# SSB_Transceiver_Antenna_Amplifier.net
KiCad netlist of a schematic drawn in EAGLE
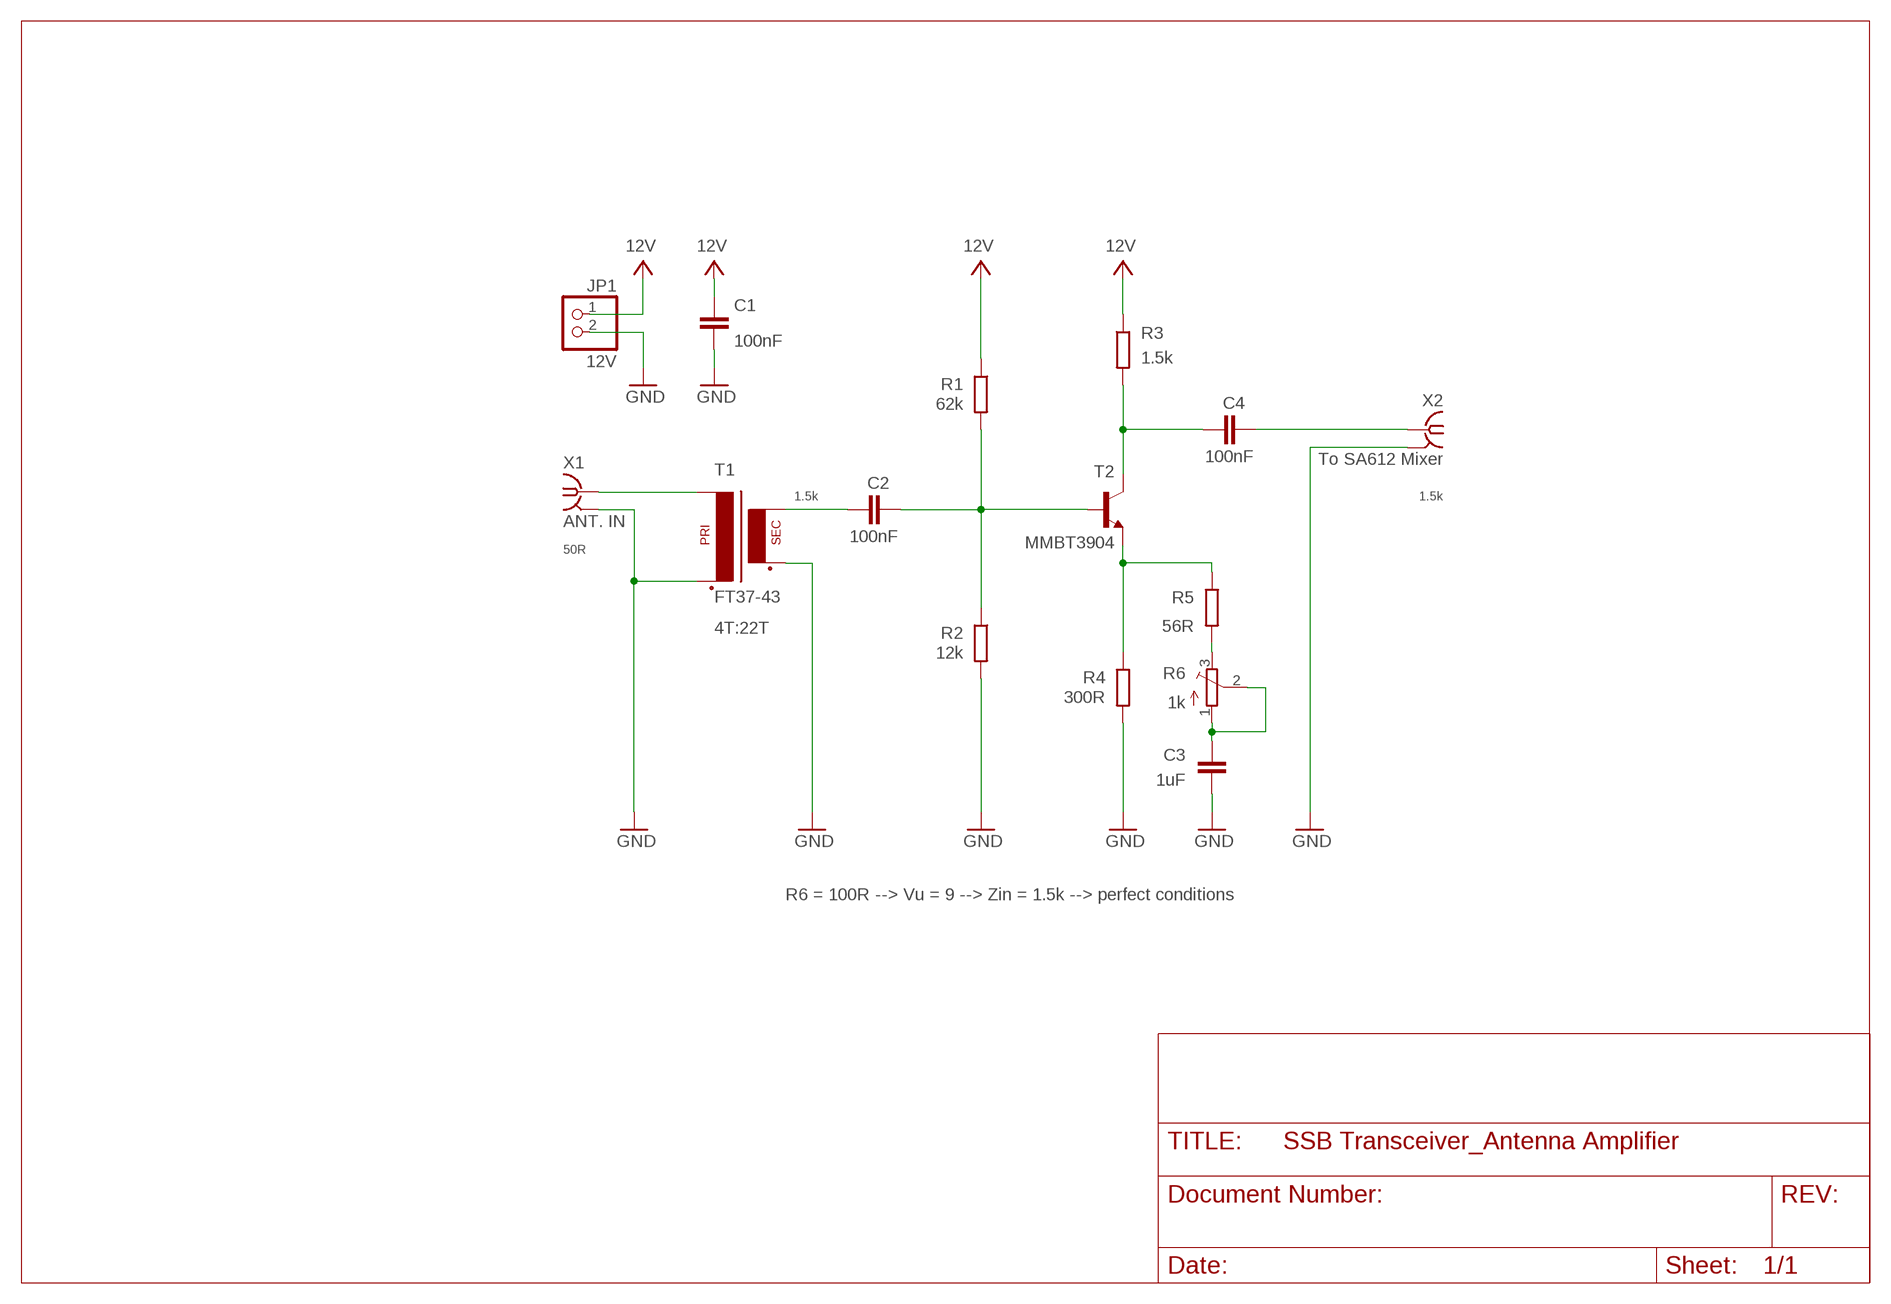
[diagram p0: schematic, sheet 1]

(export (version "E")
  (design (tool "Eeschema 10.0.6"))
  (components
    (comp (ref "C1")
      (value "100nF")
      (footprint "eagle-import:C0805")
      (libsource (lib "eagle-import") (part "C-EUC0805"))
    )
    (comp (ref "C2")
      (value "100nF")
      (footprint "eagle-import:C0805")
      (libsource (lib "eagle-import") (part "C-EUC0805"))
    )
    (comp (ref "C3")
      (value "1uF")
      (footprint "eagle-import:C0805")
      (libsource (lib "eagle-import") (part "C-EUC0805"))
    )
    (comp (ref "C4")
      (value "100nF")
      (footprint "eagle-import:C0805")
      (libsource (lib "eagle-import") (part "C-EUC0805"))
    )
    (comp (ref "JP1")
      (value "12V")
      (footprint "eagle-import:1X02")
      (libsource (lib "eagle-import") (part "PINHD-1X2"))
    )
    (comp (ref "R1")
      (value "62k")
      (footprint "eagle-import:R0805")
      (libsource (lib "eagle-import") (part "R-EU_R0805"))
    )
    (comp (ref "R2")
      (value "12k")
      (footprint "eagle-import:R0805")
      (libsource (lib "eagle-import") (part "R-EU_R0805"))
    )
    (comp (ref "R3")
      (value "1.5k")
      (footprint "eagle-import:R0805")
      (libsource (lib "eagle-import") (part "R-EU_R0805"))
    )
    (comp (ref "R4")
      (value "300R")
      (footprint "eagle-import:R0805")
      (libsource (lib "eagle-import") (part "R-EU_R0805"))
    )
    (comp (ref "R5")
      (value "56R")
      (footprint "eagle-import:R0805")
      (libsource (lib "eagle-import") (part "R-EU_R0805"))
    )
    (comp (ref "R6")
      (value "1k")
      (footprint "eagle-import:3223G")
      (libsource (lib "eagle-import") (part "TRIM_EU-3223G"))
    )
    (comp (ref "T1")
      (value "FT37-43")
      (footprint "eagle-import:FT37-43SMD")
      (libsource (lib "eagle-import") (part "FT37-43"))
    )
    (comp (ref "T2")
      (value "MMBT3904")
      (footprint "eagle-import:SOT23-BEC")
      (libsource (lib "eagle-import") (part "-NPN-SOT23-BECMMBT3904LT1"))
    )
    (comp (ref "X1")
      (value "ANT. IN")
      (footprint "eagle-import:J502-ND-142-0711-821_826")
      (fields (field (name "MF") "JOHNSON COMPONENTS") (field (name "MPN") "142-0711-821"))
      (libsource (lib "eagle-import") (part "SMA-PCB-CON142-0711-821/826"))
    )
    (comp (ref "X2")
      (value "To SA612 Mixer")
      (footprint "eagle-import:J502-ND-142-0711-821_826")
      (fields (field (name "MF") "JOHNSON COMPONENTS") (field (name "MPN") "142-0711-821"))
      (libsource (lib "eagle-import") (part "SMA-PCB-CON142-0711-821/826"))
    )
  )
  (nets
    (net (code "1") (name "12V") (class "Default")
      (node (ref "C1") (pin "2") (pinfunction "2_2") (pintype "passive"))
      (node (ref "JP1") (pin "1") (pinfunction "1_1") (pintype "passive"))
      (node (ref "R1") (pin "1") (pinfunction "1_1") (pintype "passive"))
      (node (ref "R3") (pin "1") (pinfunction "1_1") (pintype "passive"))
    )
    (net (code "2") (name "GND") (class "Default")
      (node (ref "C1") (pin "1") (pinfunction "1_1") (pintype "passive"))
      (node (ref "C3") (pin "1") (pinfunction "1_1") (pintype "passive"))
      (node (ref "JP1") (pin "2") (pinfunction "2_2") (pintype "passive"))
      (node (ref "R2") (pin "2") (pinfunction "2_2") (pintype "passive"))
      (node (ref "R4") (pin "2") (pinfunction "2_2") (pintype "passive"))
      (node (ref "T1") (pin "P$2") (pinfunction "P2_P$2") (pintype "passive"))
      (node (ref "T1") (pin "S$2") (pinfunction "S2_S$2") (pintype "passive"))
      (node (ref "X1") (pin "G@1") (pinfunction "2_G@1") (pintype "passive"))
      (node (ref "X1") (pin "G@2") (pinfunction "2_G@2") (pintype "passive"))
      (node (ref "X1") (pin "G@3") (pinfunction "2_G@3") (pintype "passive"))
      (node (ref "X1") (pin "G@4") (pinfunction "2_G@4") (pintype "passive"))
      (node (ref "X2") (pin "G@1") (pinfunction "2_G@1") (pintype "passive"))
      (node (ref "X2") (pin "G@2") (pinfunction "2_G@2") (pintype "passive"))
      (node (ref "X2") (pin "G@3") (pinfunction "2_G@3") (pintype "passive"))
      (node (ref "X2") (pin "G@4") (pinfunction "2_G@4") (pintype "passive"))
    )
    (net (code "3") (name "Net-(C2-Pad2)") (class "Default")
      (node (ref "C2") (pin "2") (pinfunction "2_2") (pintype "passive"))
      (node (ref "R1") (pin "2") (pinfunction "2_2") (pintype "passive"))
      (node (ref "R2") (pin "1") (pinfunction "1_1") (pintype "passive"))
      (node (ref "T2") (pin "B") (pinfunction "B_B") (pintype "passive"))
    )
    (net (code "4") (name "Net-(C4-Pad1)") (class "Default")
      (node (ref "C4") (pin "1") (pinfunction "1_1") (pintype "passive"))
      (node (ref "R3") (pin "2") (pinfunction "2_2") (pintype "passive"))
      (node (ref "T2") (pin "C") (pinfunction "C_C") (pintype "passive"))
    )
    (net (code "5") (name "Net-(C4-Pad2)") (class "Default")
      (node (ref "C4") (pin "2") (pinfunction "2_2") (pintype "passive"))
      (node (ref "X2") (pin "1") (pinfunction "1_1") (pintype "passive"))
    )
    (net (code "6") (name "Net-(R4-Pad1)") (class "Default")
      (node (ref "R4") (pin "1") (pinfunction "1_1") (pintype "passive"))
      (node (ref "R5") (pin "1") (pinfunction "1_1") (pintype "passive"))
      (node (ref "T2") (pin "E") (pinfunction "E_E") (pintype "passive"))
    )
    (net (code "7") (name "Net-(R6-A)") (class "Default")
      (node (ref "C3") (pin "2") (pinfunction "2_2") (pintype "passive"))
      (node (ref "R6") (pin "1") (pinfunction "A_1") (pintype "passive"))
      (node (ref "R6") (pin "2") (pinfunction "S_2") (pintype "passive"))
    )
    (net (code "8") (name "Net-(R6-E)") (class "Default")
      (node (ref "R5") (pin "2") (pinfunction "2_2") (pintype "passive"))
      (node (ref "R6") (pin "3") (pinfunction "E_3") (pintype "passive"))
    )
    (net (code "9") (name "Net-(T1-P1)") (class "Default")
      (node (ref "T1") (pin "P$1") (pinfunction "P1_P$1") (pintype "passive"))
      (node (ref "X1") (pin "1") (pinfunction "1_1") (pintype "passive"))
    )
    (net (code "10") (name "Net-(T1-S1)") (class "Default")
      (node (ref "C2") (pin "1") (pinfunction "1_1") (pintype "passive"))
      (node (ref "T1") (pin "S$1") (pinfunction "S1_S$1") (pintype "passive"))
    )
  )
)
